# LuxLogger_V2_sensors.net
KiCad netlist of a schematic drawn in Altium Designer
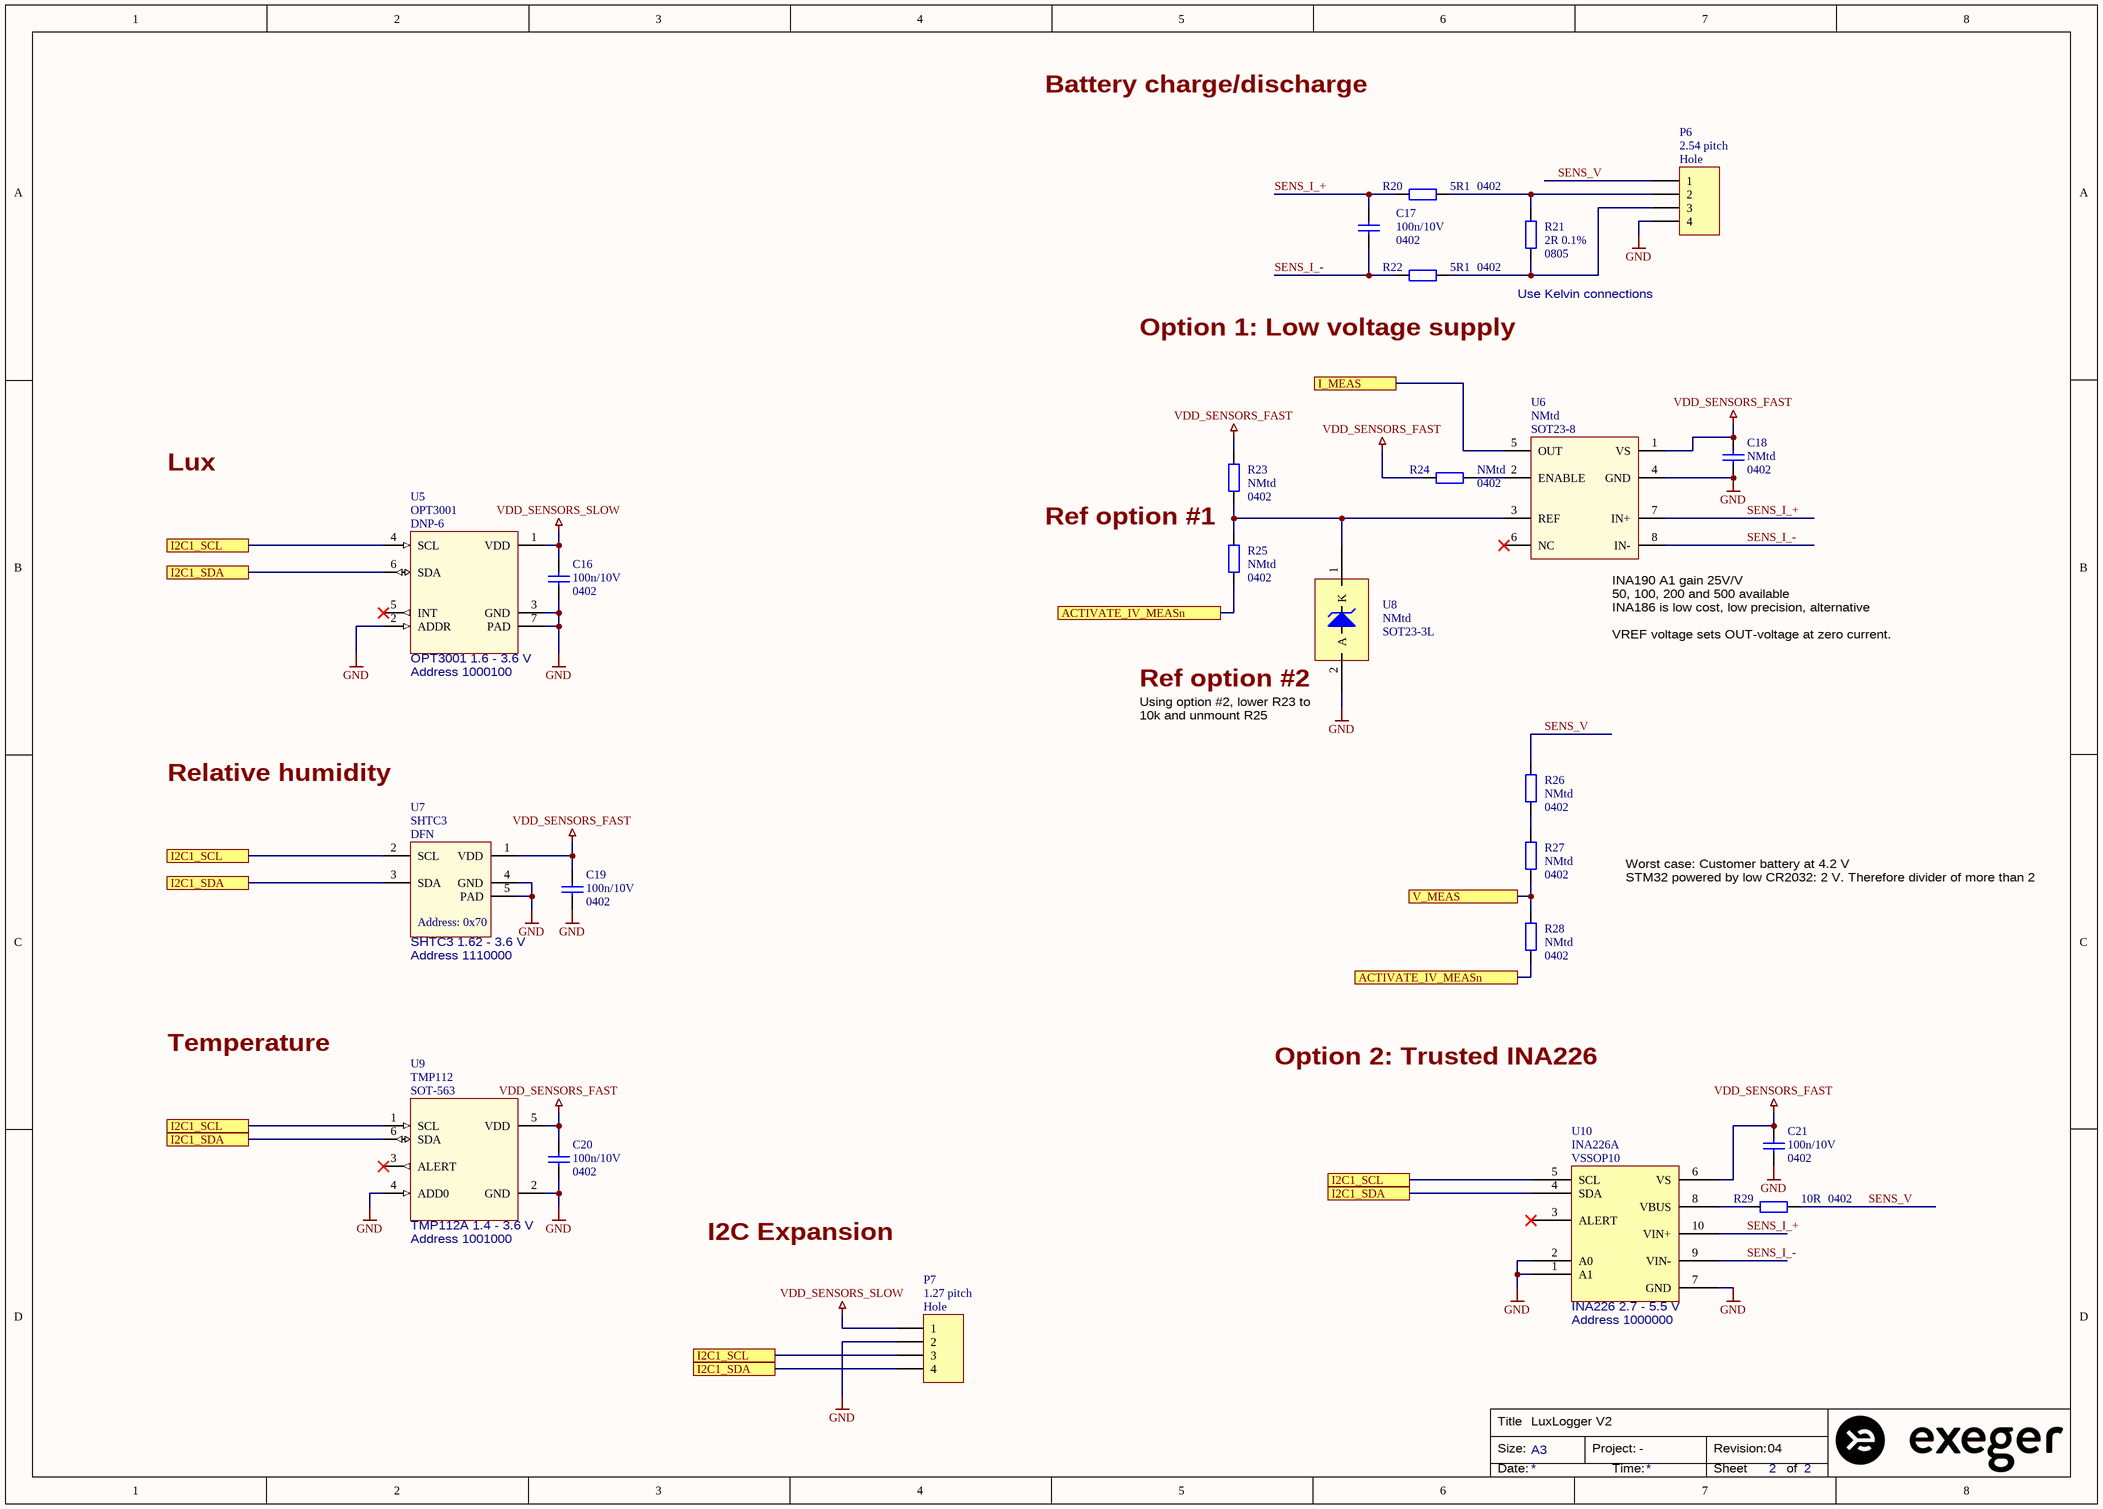
[diagram p0: LuxLogger_V2_sensors.SchDoc]

(export (version "E")
  (design (tool "Eeschema 10.0.6"))
  (components
    (comp (ref "C16")
      (value "~")
      (footprint "CAP0402")
      (description "Capacitor")
      (fields (field (name "SPECIFICATION") "100n/10V") (field (name "PACKAGE") "0402"))
      (libsource (lib "Miscellaneous Devices") (part "Cap"))
    )
    (comp (ref "C17")
      (value "~")
      (footprint "CAP0402")
      (description "Capacitor")
      (fields (field (name "SPECIFICATION") "100n/10V") (field (name "PACKAGE") "0402"))
      (libsource (lib "Miscellaneous Devices") (part "Cap"))
    )
    (comp (ref "C18")
      (value "100n/10V")
      (footprint "CAP0402")
      (description "Capacitor")
      (fields (field (name "SPECIFICATION") "NMtd") (field (name "PACKAGE") "0402"))
      (libsource (lib "Miscellaneous Devices") (part "Cap"))
    )
    (comp (ref "C19")
      (value "~")
      (footprint "CAP0402")
      (description "Capacitor")
      (fields (field (name "SPECIFICATION") "100n/10V") (field (name "PACKAGE") "0402"))
      (libsource (lib "Miscellaneous Devices") (part "Cap"))
    )
    (comp (ref "C20")
      (value "~")
      (footprint "CAP0402")
      (description "Capacitor")
      (fields (field (name "SPECIFICATION") "100n/10V") (field (name "PACKAGE") "0402"))
      (libsource (lib "Miscellaneous Devices") (part "Cap"))
    )
    (comp (ref "C21")
      (value "~")
      (footprint "CAP0402")
      (description "Capacitor")
      (fields (field (name "SPECIFICATION") "100n/10V") (field (name "PACKAGE") "0402"))
      (libsource (lib "Miscellaneous Devices") (part "Cap"))
    )
    (comp (ref "P6")
      (value "~")
      (footprint "Header 1x4 2.54")
      (description "Header, 4-Pin")
      (fields (field (name "SPECIFICATION") "2.54 pitch") (field (name "PACKAGE") "Hole"))
      (libsource (lib "Miscellaneous Connectors") (part "Header 4"))
    )
    (comp (ref "P7")
      (value "~")
      (footprint "Header 1x4 1.27")
      (description "Header, 4-Pin")
      (fields (field (name "SPECIFICATION") "1.27 pitch") (field (name "PACKAGE") "Hole"))
      (libsource (lib "Miscellaneous Connectors") (part "Header 4"))
    )
    (comp (ref "R20")
      (value "~")
      (footprint "RES0402")
      (description "Resistor")
      (fields (field (name "PACKAGE") "0402") (field (name "SPECIFICATION") "5R1"))
      (libsource (lib "Miscellaneous Devices") (part "Res2"))
    )
    (comp (ref "R21")
      (value "~")
      (footprint "RES0805")
      (description "Resistor")
      (fields (field (name "PACKAGE") "0805") (field (name "SPECIFICATION") "2R 0.1%"))
      (libsource (lib "") (part "Res2_1"))
    )
    (comp (ref "R22")
      (value "~")
      (footprint "RES0402")
      (description "Resistor")
      (fields (field (name "PACKAGE") "0402") (field (name "SPECIFICATION") "5R1"))
      (libsource (lib "Miscellaneous Devices") (part "Res2"))
    )
    (comp (ref "R23")
      (value "100k 0.1%")
      (footprint "RES0402")
      (description "Resistor")
      (fields (field (name "PACKAGE") "0402") (field (name "SPECIFICATION") "NMtd"))
      (libsource (lib "") (part "Res2_1"))
    )
    (comp (ref "R24")
      (value "0R")
      (footprint "RES0402")
      (description "Resistor")
      (fields (field (name "PACKAGE") "0402") (field (name "SPECIFICATION") "NMtd"))
      (libsource (lib "Miscellaneous Devices") (part "Res2"))
    )
    (comp (ref "R25")
      (value "100k 0.1%")
      (footprint "RES0402")
      (description "Resistor")
      (fields (field (name "PACKAGE") "0402") (field (name "SPECIFICATION") "NMtd"))
      (libsource (lib "") (part "Res2_1"))
    )
    (comp (ref "R26")
      (value "10k 0.1%")
      (footprint "RES0402")
      (description "Resistor")
      (fields (field (name "PACKAGE") "0402") (field (name "SPECIFICATION") "NMtd"))
      (libsource (lib "") (part "Res2_1"))
    )
    (comp (ref "R27")
      (value "100k 0.1%")
      (footprint "RES0402")
      (description "Resistor")
      (fields (field (name "PACKAGE") "0402") (field (name "SPECIFICATION") "NMtd"))
      (libsource (lib "") (part "Res2_1"))
    )
    (comp (ref "R28")
      (value "100k 0.1%")
      (footprint "RES0402")
      (description "Resistor")
      (fields (field (name "PACKAGE") "0402") (field (name "SPECIFICATION") "NMtd"))
      (libsource (lib "") (part "Res2_1"))
    )
    (comp (ref "R29")
      (value "~")
      (footprint "RES0402")
      (description "Resistor")
      (fields (field (name "PACKAGE") "0402") (field (name "SPECIFICATION") "10R"))
      (libsource (lib "Miscellaneous Devices") (part "Res2"))
    )
    (comp (ref "U5")
      (value "~")
      (footprint "OPT3001")
      (description "Lux sensor")
      (fields
        (field (name "MANUFACTURER") "TI")
        (field (name "SPECIFICATION") "OPT3001")
        (field (name "PACKAGE") "DNP-6")
      )
      (libsource (lib "Exeger_schematic_library") (part "OPT3001"))
    )
    (comp (ref "U6")
      (value "~")
      (footprint "SOT23-8")
      (description "Current amplifier")
      (fields
        (field (name "MANUFACTURER") "TI")
        (field (name "PACKAGE") "SOT23-8")
        (field (name "SPECIFICATION") "NMtd")
      )
      (libsource (lib "Exeger_schematic_library") (part "INA190"))
    )
    (comp (ref "U7")
      (value "~")
      (footprint "SHTC3")
      (description "SHTC3 RH sensor")
      (fields
        (field (name "MANUFACTURER") "SENSIRION")
        (field (name "SPECIFICATION") "SHTC3")
        (field (name "PACKAGE") "DFN")
      )
      (libsource (lib "Exeger_schematic_library") (part "SHTC3"))
    )
    (comp (ref "U8")
      (value "~")
      (footprint "SOT23-3")
      (description "Shunt voltage reference")
      (fields
        (field (name "MANUFACTURER") "ST")
        (field (name "PACKAGE") "SOT23-3L")
        (field (name "SPECIFICATION") "NMtd")
      )
      (libsource (lib "Exeger_schematic_library") (part "TS4061"))
    )
    (comp (ref "U9")
      (value "~")
      (footprint "SOTFL50P160X60-6N")
      (description "Temp_Sensor")
      (fields
        (field (name "PACKAGE") "SOT-563")
        (field (name "SPECIFICATION") "TMP112")
        (field (name "MANUFACTURER") "TI")
      )
      (libsource (lib "Exeger_schematic_library") (part "TMP112A"))
    )
    (comp (ref "U10")
      (value "~")
      (footprint "VSSOP-10")
      (description "Current and power monitor")
      (fields
        (field (name "MANUFACTURER") "TI")
        (field (name "PACKAGE") "VSSOP10")
        (field (name "SPECIFICATION") "INA226A")
      )
      (libsource (lib "Exeger_schematic_library") (part "INA226"))
    )
  )
  (nets
    (net (code "1") (name "/ACTIVATE_IV_MEASn") (class "Default")
      (node (ref "R25") (pin "2") (pinfunction "2_2") (pintype "passive"))
      (node (ref "R28") (pin "2") (pinfunction "2_2") (pintype "passive"))
    )
    (net (code "2") (name "/I2C1_SCL") (class "Default")
      (node (ref "P7") (pin "3") (pinfunction "3_3") (pintype "passive"))
      (node (ref "U10") (pin "5") (pinfunction "SCL_5") (pintype "passive"))
      (node (ref "U5") (pin "4") (pinfunction "SCL_4") (pintype "input"))
      (node (ref "U7") (pin "2") (pinfunction "SCL_2") (pintype "passive"))
      (node (ref "U9") (pin "1") (pinfunction "SCL_1") (pintype "input"))
    )
    (net (code "3") (name "/I2C1_SDA") (class "Default")
      (node (ref "P7") (pin "4") (pinfunction "4_4") (pintype "passive"))
      (node (ref "U10") (pin "4") (pinfunction "SDA_4") (pintype "passive"))
      (node (ref "U5") (pin "6") (pinfunction "SDA_6") (pintype "bidirectional"))
      (node (ref "U7") (pin "3") (pinfunction "SDA_3") (pintype "passive"))
      (node (ref "U9") (pin "6") (pinfunction "SDA_6") (pintype "bidirectional"))
    )
    (net (code "4") (name "/I_MEAS") (class "Default")
      (node (ref "U6") (pin "5") (pinfunction "OUT_5") (pintype "passive"))
    )
    (net (code "5") (name "/SENS_I_+") (class "Default")
      (node (ref "C17") (pin "2") (pinfunction "2_2") (pintype "passive"))
      (node (ref "R20") (pin "2") (pinfunction "2_2") (pintype "passive"))
      (node (ref "U10") (pin "10") (pinfunction "VIN+_10") (pintype "passive"))
      (node (ref "U6") (pin "7") (pinfunction "IN+_7") (pintype "passive"))
    )
    (net (code "6") (name "/SENS_I_-") (class "Default")
      (node (ref "C17") (pin "1") (pinfunction "1_1") (pintype "passive"))
      (node (ref "R22") (pin "2") (pinfunction "2_2") (pintype "passive"))
      (node (ref "U10") (pin "9") (pinfunction "VIN-_9") (pintype "passive"))
      (node (ref "U6") (pin "8") (pinfunction "IN-_8") (pintype "passive"))
    )
    (net (code "7") (name "/SENS_V") (class "Default")
      (node (ref "P6") (pin "1") (pinfunction "1_1") (pintype "passive"))
      (node (ref "R26") (pin "1") (pinfunction "1_1") (pintype "passive"))
      (node (ref "R29") (pin "1") (pinfunction "1_1") (pintype "passive"))
    )
    (net (code "8") (name "/V_MEAS") (class "Default")
      (node (ref "R27") (pin "2") (pinfunction "2_2") (pintype "passive"))
      (node (ref "R28") (pin "1") (pinfunction "1_1") (pintype "passive"))
    )
    (net (code "9") (name "GND") (class "Default")
      (node (ref "C16") (pin "1") (pinfunction "1_1") (pintype "passive"))
      (node (ref "C18") (pin "1") (pinfunction "1_1") (pintype "passive"))
      (node (ref "C19") (pin "1") (pinfunction "1_1") (pintype "passive"))
      (node (ref "C20") (pin "1") (pinfunction "1_1") (pintype "passive"))
      (node (ref "C21") (pin "1") (pinfunction "1_1") (pintype "passive"))
      (node (ref "P6") (pin "4") (pinfunction "4_4") (pintype "passive"))
      (node (ref "P7") (pin "2") (pinfunction "2_2") (pintype "passive"))
      (node (ref "U10") (pin "1") (pinfunction "A1_1") (pintype "passive"))
      (node (ref "U10") (pin "2") (pinfunction "A0_2") (pintype "passive"))
      (node (ref "U10") (pin "7") (pinfunction "GND_7") (pintype "passive"))
      (node (ref "U5") (pin "2") (pinfunction "ADDR_2") (pintype "input"))
      (node (ref "U5") (pin "3") (pinfunction "GND_3") (pintype "power_in"))
      (node (ref "U5") (pin "7") (pinfunction "PAD_7") (pintype "power_in"))
      (node (ref "U6") (pin "4") (pinfunction "GND_4") (pintype "passive"))
      (node (ref "U7") (pin "4") (pinfunction "GND_4") (pintype "passive"))
      (node (ref "U7") (pin "5") (pinfunction "PAD_5") (pintype "passive"))
      (node (ref "U8") (pin "2") (pinfunction "A_2") (pintype "passive"))
      (node (ref "U9") (pin "2") (pinfunction "GND_2") (pintype "power_in"))
      (node (ref "U9") (pin "4") (pinfunction "ADD0_4") (pintype "input"))
    )
    (net (code "10") (name "Net-(P6-Pad2)") (class "Default")
      (node (ref "P6") (pin "2") (pinfunction "2_2") (pintype "passive"))
      (node (ref "R20") (pin "1") (pinfunction "1_1") (pintype "passive"))
      (node (ref "R21") (pin "1") (pinfunction "1_1") (pintype "passive"))
    )
    (net (code "11") (name "Net-(P6-Pad3)") (class "Default")
      (node (ref "P6") (pin "3") (pinfunction "3_3") (pintype "passive"))
      (node (ref "R21") (pin "2") (pinfunction "2_2") (pintype "passive"))
      (node (ref "R22") (pin "1") (pinfunction "1_1") (pintype "passive"))
    )
    (net (code "12") (name "Net-(R26-Pad2)") (class "Default")
      (node (ref "R26") (pin "2") (pinfunction "2_2") (pintype "passive"))
      (node (ref "R27") (pin "1") (pinfunction "1_1") (pintype "passive"))
    )
    (net (code "13") (name "Net-(U6-ENABLE)") (class "Default")
      (node (ref "R24") (pin "1") (pinfunction "1_1") (pintype "passive"))
      (node (ref "U6") (pin "2") (pinfunction "ENABLE_2") (pintype "passive"))
    )
    (net (code "14") (name "Net-(U6-REF)") (class "Default")
      (node (ref "R23") (pin "2") (pinfunction "2_2") (pintype "passive"))
      (node (ref "R25") (pin "1") (pinfunction "1_1") (pintype "passive"))
      (node (ref "U6") (pin "3") (pinfunction "REF_3") (pintype "passive"))
      (node (ref "U8") (pin "1") (pinfunction "K_1") (pintype "passive"))
    )
    (net (code "15") (name "Net-(U10-VBUS)") (class "Default")
      (node (ref "R29") (pin "2") (pinfunction "2_2") (pintype "passive"))
      (node (ref "U10") (pin "8") (pinfunction "VBUS_8") (pintype "passive"))
    )
    (net (code "16") (name "VDD_SENSORS_FAST") (class "Default")
      (node (ref "C18") (pin "2") (pinfunction "2_2") (pintype "passive"))
      (node (ref "C19") (pin "2") (pinfunction "2_2") (pintype "passive"))
      (node (ref "C20") (pin "2") (pinfunction "2_2") (pintype "passive"))
      (node (ref "C21") (pin "2") (pinfunction "2_2") (pintype "passive"))
      (node (ref "R23") (pin "1") (pinfunction "1_1") (pintype "passive"))
      (node (ref "R24") (pin "2") (pinfunction "2_2") (pintype "passive"))
      (node (ref "U10") (pin "6") (pinfunction "VS_6") (pintype "passive"))
      (node (ref "U6") (pin "1") (pinfunction "VS_1") (pintype "passive"))
      (node (ref "U7") (pin "1") (pinfunction "VDD_1") (pintype "passive"))
      (node (ref "U9") (pin "5") (pinfunction "VDD_5") (pintype "power_in"))
    )
    (net (code "17") (name "VDD_SENSORS_SLOW") (class "Default")
      (node (ref "C16") (pin "2") (pinfunction "2_2") (pintype "passive"))
      (node (ref "P7") (pin "1") (pinfunction "1_1") (pintype "passive"))
      (node (ref "U5") (pin "1") (pinfunction "VDD_1") (pintype "power_in"))
    )
    (net (code "18") (name "unconnected-(U5-INT-Pad5)") (class "Default")
      (node (ref "U5") (pin "5") (pinfunction "INT_5") (pintype "output+no_connect"))
    )
    (net (code "19") (name "unconnected-(U6-NC-Pad6)") (class "Default")
      (node (ref "U6") (pin "6") (pinfunction "NC_6") (pintype "passive+no_connect"))
    )
    (net (code "20") (name "unconnected-(U9-ALERT-Pad3)") (class "Default")
      (node (ref "U9") (pin "3") (pinfunction "ALERT_3") (pintype "output+no_connect"))
    )
    (net (code "21") (name "unconnected-(U10-ALERT-Pad3)") (class "Default")
      (node (ref "U10") (pin "3") (pinfunction "ALERT_3") (pintype "passive+no_connect"))
    )
  )
)
